# header2313.net
KiCad netlist of a schematic drawn in EAGLE
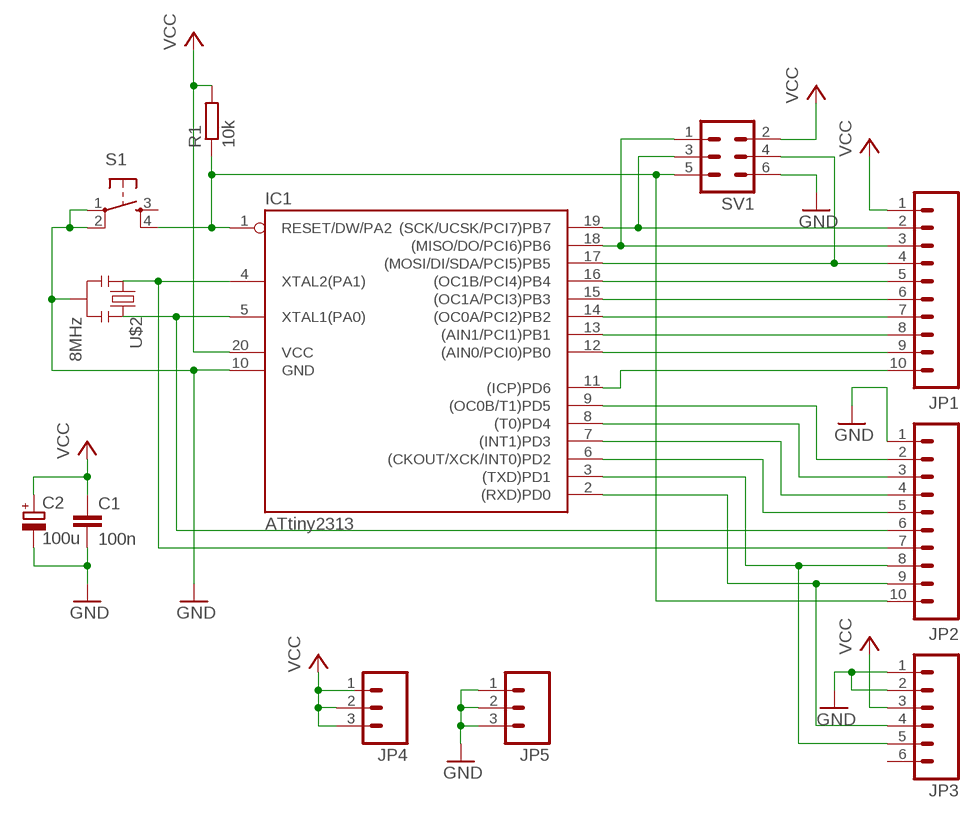
[diagram p0: schematic, sheet 1]

(export (version "E")
  (design (tool "Eeschema 10.0.6"))
  (components
    (comp (ref "C1")
      (value "100n")
      (footprint "eagle-import:C025-025X050")
      (libsource (lib "eagle-import") (part "C-EU025-025X050"))
    )
    (comp (ref "C2")
      (value "100u")
      (footprint "eagle-import:E2,5-5")
      (libsource (lib "eagle-import") (part "CPOL-EUE2.5-5"))
    )
    (comp (ref "IC1")
      (value "ATtiny2313")
      (footprint "eagle-import:DIL20")
      (libsource (lib "eagle-import") (part "ATTINY2313P-20"))
    )
    (comp (ref "JP1")
      (value "M100.1")
      (footprint "eagle-import:1X10")
      (libsource (lib "eagle-import") (part "M100.1"))
    )
    (comp (ref "JP2")
      (value "M100.1")
      (footprint "eagle-import:1X10")
      (libsource (lib "eagle-import") (part "M100.1"))
    )
    (comp (ref "JP3")
      (value "M06SIP")
      (footprint "eagle-import:1X06")
      (libsource (lib "eagle-import") (part "M06SIP"))
    )
    (comp (ref "JP4")
      (value "M03PTH")
      (footprint "eagle-import:1X03")
      (libsource (lib "eagle-import") (part "M03PTH"))
    )
    (comp (ref "JP5")
      (value "M03PTH")
      (footprint "eagle-import:1X03")
      (libsource (lib "eagle-import") (part "M03PTH"))
    )
    (comp (ref "R1")
      (value "10k")
      (footprint "eagle-import:0207_10")
      (libsource (lib "eagle-import") (part "R-EU_0207/10"))
    )
    (comp (ref "S1")
      (value "TAC_SWITCHPTH")
      (footprint "eagle-import:TACTILE-PTH")
      (libsource (lib "eagle-import") (part "TAC_SWITCHPTH"))
    )
    (comp (ref "SV1")
      (value "MA03-2")
      (footprint "eagle-import:MA03-2")
      (libsource (lib "eagle-import") (part "MA03-2"))
    )
    (comp (ref "U$2")
      (value "8MHz")
      (footprint "eagle-import:RESONATOR-PTH")
      (libsource (lib "eagle-import") (part "RESONATORPTH"))
    )
  )
  (nets
    (net (code "1") (name "GND") (class "Default")
      (node (ref "C1") (pin "2") (pinfunction "2_2") (pintype "passive"))
      (node (ref "C2") (pin "-") (pinfunction "-_-") (pintype "passive"))
      (node (ref "IC1") (pin "10") (pinfunction "GND_10") (pintype "power_in"))
      (node (ref "JP2") (pin "1") (pinfunction "1_1") (pintype "passive"))
      (node (ref "JP3") (pin "1") (pinfunction "1_1") (pintype "passive"))
      (node (ref "JP3") (pin "2") (pinfunction "2_2") (pintype "passive"))
      (node (ref "JP5") (pin "1") (pinfunction "1_1") (pintype "passive"))
      (node (ref "JP5") (pin "2") (pinfunction "2_2") (pintype "passive"))
      (node (ref "JP5") (pin "3") (pinfunction "3_3") (pintype "passive"))
      (node (ref "S1") (pin "1") (pinfunction "1_1") (pintype "passive"))
      (node (ref "S1") (pin "2") (pinfunction "2_2") (pintype "passive"))
      (node (ref "SV1") (pin "6") (pinfunction "6_6") (pintype "passive"))
      (node (ref "U$2") (pin "2") (pinfunction "2_2") (pintype "passive"))
    )
    (net (code "2") (name "Net-(IC1-(AIN0{slash}PCI0)PB0)") (class "Default")
      (node (ref "IC1") (pin "12") (pinfunction "(AIN0/PCI0)PB0_12") (pintype "bidirectional"))
      (node (ref "JP1") (pin "9") (pinfunction "9_9") (pintype "passive"))
    )
    (net (code "3") (name "Net-(IC1-(AIN1{slash}PCI1)PB1)") (class "Default")
      (node (ref "IC1") (pin "13") (pinfunction "(AIN1/PCI1)PB1_13") (pintype "bidirectional"))
      (node (ref "JP1") (pin "8") (pinfunction "8_8") (pintype "passive"))
    )
    (net (code "4") (name "Net-(IC1-(CKOUT{slash}XCK{slash}INT0)PD2)") (class "Default")
      (node (ref "IC1") (pin "6") (pinfunction "(CKOUT/XCK/INT0)PD2_6") (pintype "bidirectional"))
      (node (ref "JP2") (pin "5") (pinfunction "5_5") (pintype "passive"))
    )
    (net (code "5") (name "Net-(IC1-(ICP)PD6)") (class "Default")
      (node (ref "IC1") (pin "11") (pinfunction "(ICP)PD6_11") (pintype "bidirectional"))
      (node (ref "JP1") (pin "10") (pinfunction "10_10") (pintype "passive"))
    )
    (net (code "6") (name "Net-(IC1-(INT1)PD3)") (class "Default")
      (node (ref "IC1") (pin "7") (pinfunction "(INT1)PD3_7") (pintype "bidirectional"))
      (node (ref "JP2") (pin "4") (pinfunction "4_4") (pintype "passive"))
    )
    (net (code "7") (name "Net-(IC1-(MISO{slash}DO{slash}PCI6)PB6)") (class "Default")
      (node (ref "IC1") (pin "18") (pinfunction "(MISO/DO/PCI6)PB6_18") (pintype "bidirectional"))
      (node (ref "JP1") (pin "3") (pinfunction "3_3") (pintype "passive"))
      (node (ref "SV1") (pin "1") (pinfunction "1_1") (pintype "passive"))
    )
    (net (code "8") (name "Net-(IC1-(MOSI{slash}DI{slash}SDA{slash}PCI5)PB5)") (class "Default")
      (node (ref "IC1") (pin "17") (pinfunction "(MOSI/DI/SDA/PCI5)PB5_17") (pintype "bidirectional"))
      (node (ref "JP1") (pin "4") (pinfunction "4_4") (pintype "passive"))
      (node (ref "SV1") (pin "4") (pinfunction "4_4") (pintype "passive"))
    )
    (net (code "9") (name "Net-(IC1-(OC0A{slash}PCI2)PB2)") (class "Default")
      (node (ref "IC1") (pin "14") (pinfunction "(OC0A/PCI2)PB2_14") (pintype "bidirectional"))
      (node (ref "JP1") (pin "7") (pinfunction "7_7") (pintype "passive"))
    )
    (net (code "10") (name "Net-(IC1-(OC0B{slash}T1)PD5)") (class "Default")
      (node (ref "IC1") (pin "9") (pinfunction "(OC0B/T1)PD5_9") (pintype "bidirectional"))
      (node (ref "JP2") (pin "2") (pinfunction "2_2") (pintype "passive"))
    )
    (net (code "11") (name "Net-(IC1-(OC1A{slash}PCI3)PB3)") (class "Default")
      (node (ref "IC1") (pin "15") (pinfunction "(OC1A/PCI3)PB3_15") (pintype "bidirectional"))
      (node (ref "JP1") (pin "6") (pinfunction "6_6") (pintype "passive"))
    )
    (net (code "12") (name "Net-(IC1-(OC1B{slash}PCI4)PB4)") (class "Default")
      (node (ref "IC1") (pin "16") (pinfunction "(OC1B/PCI4)PB4_16") (pintype "bidirectional"))
      (node (ref "JP1") (pin "5") (pinfunction "5_5") (pintype "passive"))
    )
    (net (code "13") (name "Net-(IC1-(RXD)PD0)") (class "Default")
      (node (ref "IC1") (pin "2") (pinfunction "(RXD)PD0_2") (pintype "bidirectional"))
      (node (ref "JP2") (pin "9") (pinfunction "9_9") (pintype "passive"))
      (node (ref "JP3") (pin "4") (pinfunction "4_4") (pintype "passive"))
    )
    (net (code "14") (name "Net-(IC1-(SCK{slash}UCSK{slash}PCI7)PB7)") (class "Default")
      (node (ref "IC1") (pin "19") (pinfunction "(SCK/UCSK/PCI7)PB7_19") (pintype "bidirectional"))
      (node (ref "JP1") (pin "2") (pinfunction "2_2") (pintype "passive"))
      (node (ref "SV1") (pin "3") (pinfunction "3_3") (pintype "passive"))
    )
    (net (code "15") (name "Net-(IC1-(T0)PD4)") (class "Default")
      (node (ref "IC1") (pin "8") (pinfunction "(T0)PD4_8") (pintype "bidirectional"))
      (node (ref "JP2") (pin "3") (pinfunction "3_3") (pintype "passive"))
    )
    (net (code "16") (name "Net-(IC1-(TXD)PD1)") (class "Default")
      (node (ref "IC1") (pin "3") (pinfunction "(TXD)PD1_3") (pintype "bidirectional"))
      (node (ref "JP2") (pin "8") (pinfunction "8_8") (pintype "passive"))
      (node (ref "JP3") (pin "5") (pinfunction "5_5") (pintype "passive"))
    )
    (net (code "17") (name "Net-(IC1-RESET{slash}DW{slash}PA2)") (class "Default")
      (node (ref "IC1") (pin "1") (pinfunction "RESET/DW/PA2_1") (pintype "bidirectional"))
      (node (ref "JP2") (pin "10") (pinfunction "10_10") (pintype "passive"))
      (node (ref "R1") (pin "1") (pinfunction "1_1") (pintype "passive"))
      (node (ref "S1") (pin "4") (pinfunction "4_4") (pintype "passive"))
      (node (ref "SV1") (pin "5") (pinfunction "5_5") (pintype "passive"))
    )
    (net (code "18") (name "Net-(IC1-XTAL1(PA0))") (class "Default")
      (node (ref "IC1") (pin "5") (pinfunction "XTAL1(PA0)_5") (pintype "bidirectional"))
      (node (ref "JP2") (pin "6") (pinfunction "6_6") (pintype "passive"))
      (node (ref "U$2") (pin "3") (pinfunction "3_3") (pintype "passive"))
    )
    (net (code "19") (name "Net-(IC1-XTAL2(PA1))") (class "Default")
      (node (ref "IC1") (pin "4") (pinfunction "XTAL2(PA1)_4") (pintype "bidirectional"))
      (node (ref "JP2") (pin "7") (pinfunction "7_7") (pintype "passive"))
      (node (ref "U$2") (pin "1") (pinfunction "1_1") (pintype "passive"))
    )
    (net (code "20") (name "VCC") (class "Default")
      (node (ref "C1") (pin "1") (pinfunction "1_1") (pintype "passive"))
      (node (ref "C2") (pin "+") (pinfunction "+_+") (pintype "passive"))
      (node (ref "IC1") (pin "20") (pinfunction "VCC_20") (pintype "power_in"))
      (node (ref "JP1") (pin "1") (pinfunction "1_1") (pintype "passive"))
      (node (ref "JP3") (pin "3") (pinfunction "3_3") (pintype "passive"))
      (node (ref "JP4") (pin "1") (pinfunction "1_1") (pintype "passive"))
      (node (ref "JP4") (pin "2") (pinfunction "2_2") (pintype "passive"))
      (node (ref "JP4") (pin "3") (pinfunction "3_3") (pintype "passive"))
      (node (ref "R1") (pin "2") (pinfunction "2_2") (pintype "passive"))
      (node (ref "SV1") (pin "2") (pinfunction "2_2") (pintype "passive"))
    )
    (net (code "21") (name "unconnected-(JP3-Pad6)") (class "Default")
      (node (ref "JP3") (pin "6") (pinfunction "6_6") (pintype "passive"))
    )
    (net (code "22") (name "unconnected-(S1-Pad3)") (class "Default")
      (node (ref "S1") (pin "3") (pinfunction "3_3") (pintype "passive"))
    )
  )
)
